# design.net
KiCad netlist of a schematic drawn in Altium Designer
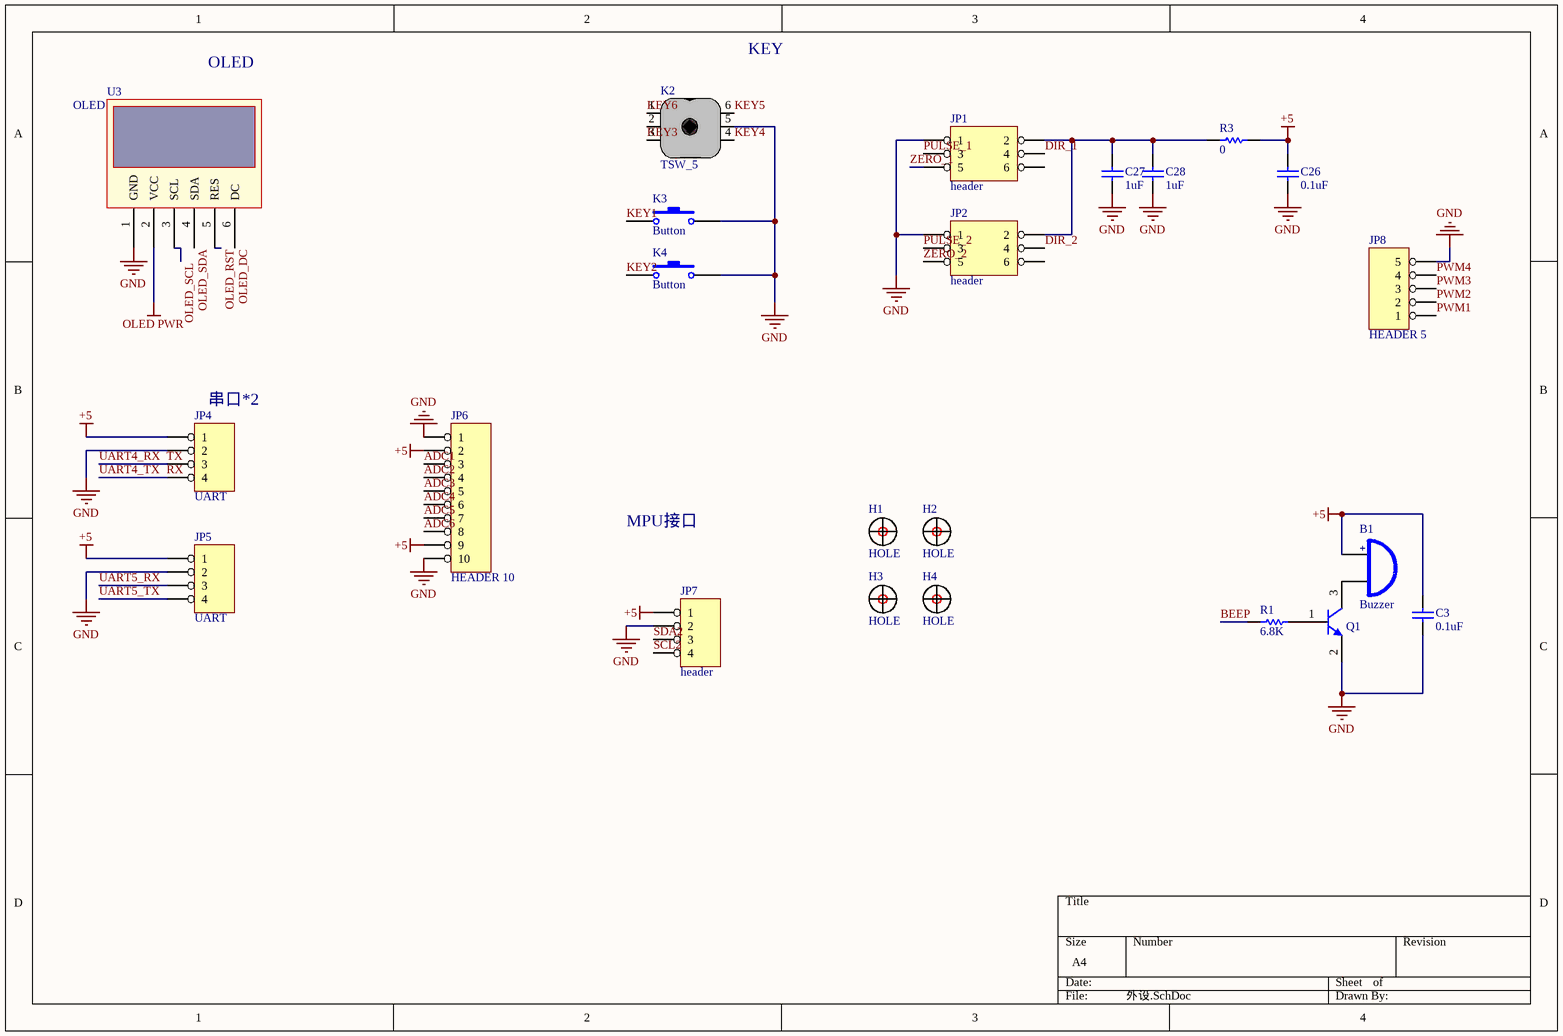
[diagram p0: 外设.SchDoc]

(export (version "E")
  (design (tool "Eeschema 10.0.6"))
  (components
    (comp (ref "B1") (value "Buzzer") (footprint "BUZZ") (libsource (lib "mylib") (part "Buzzer")))
    (comp (ref "C3")
      (value "0.1uF")
      (footprint "0603_C")
      (description "Capacitor")
      (fields (field (name "PUBLISHER") "Altium Limited"))
      (libsource (lib "My Footprint") (part "CAP"))
    )
    (comp (ref "C26")
      (value "0.1uF")
      (footprint "0805_c")
      (description "Capacitor")
      (fields (field (name "PUBLISHER") "Altium Limited"))
      (libsource (lib "LY御用集成库") (part "CAP"))
    )
    (comp (ref "C27")
      (value "1uF")
      (footprint "0805_c")
      (description "Capacitor")
      (fields (field (name "PUBLISHER") "Altium Limited"))
      (libsource (lib "LY御用集成库") (part "CAP"))
    )
    (comp (ref "C28")
      (value "1uF")
      (footprint "0805_c")
      (description "Capacitor")
      (fields (field (name "PUBLISHER") "Altium Limited"))
      (libsource (lib "LY御用集成库") (part "CAP"))
    )
    (comp (ref "H1") (value "HOLE") (footprint "定位孔 Φ3 1") (libsource (lib "LY御用集成库") (part "HOLE")))
    (comp (ref "H2") (value "HOLE") (footprint "定位孔 Φ3 1") (libsource (lib "LY御用集成库") (part "HOLE")))
    (comp (ref "H3") (value "HOLE") (footprint "定位孔 Φ3 1") (libsource (lib "LY御用集成库") (part "HOLE")))
    (comp (ref "H4") (value "HOLE") (footprint "定位孔 Φ3 1") (libsource (lib "LY御用集成库") (part "HOLE")))
    (comp (ref "JP1")
      (value "header")
      (footprint "header2X3")
      (libsource (lib "LY御用集成库") (part "HEADER 3X2"))
    )
    (comp (ref "JP2")
      (value "header")
      (footprint "header2X3")
      (libsource (lib "LY御用集成库") (part "HEADER 3X2"))
    )
    (comp (ref "JP4") (value "UART") (footprint "header4_M") (libsource (lib "LY御用集成库") (part "HEADER 4")))
    (comp (ref "JP5") (value "UART") (footprint "header4") (libsource (lib "LY御用集成库") (part "HEADER 4")))
    (comp (ref "JP6")
      (value "HEADER 10")
      (footprint "HEADER_10P_1.25_UP")
      (libsource (lib "LY御用集成库") (part "HEADER 10"))
    )
    (comp (ref "JP7") (value "header") (footprint "header4") (libsource (lib "LY御用集成库") (part "HEADER 4")))
    (comp (ref "JP8")
      (value "HEADER 5")
      (footprint "HEADER_5P_1.25_RT")
      (libsource (lib "LY御用集成库") (part "HEADER 5"))
    )
    (comp (ref "K2")
      (value "TSW_5")
      (footprint "TSW-10")
      (description "方向开关")
      (libsource (lib "LY御用集成库") (part "TSW_5"))
    )
    (comp (ref "K3")
      (value "Button")
      (footprint "button_2")
      (fields (field (name "PUBLISHER") "Altium Limited"))
      (libsource (lib "LY御用集成库") (part "Button"))
    )
    (comp (ref "K4")
      (value "Button")
      (footprint "button_2")
      (fields (field (name "PUBLISHER") "Altium Limited"))
      (libsource (lib "LY御用集成库") (part "Button"))
    )
    (comp (ref "Q1")
      (value "NPN2")
      (footprint "SOT-23-3")
      (description "贴片")
      (libsource (lib "mylib") (part "NPN2"))
    )
    (comp (ref "R1") (value "6.8K") (footprint "R0603") (libsource (lib "mylib") (part "RES")))
    (comp (ref "R3")
      (value "0")
      (footprint "R0603")
      (description "Resistor")
      (fields (field (name "PUBLISHER") "Altium Limited"))
      (libsource (lib "LY御用集成库") (part "RES"))
    )
    (comp (ref "U3")
      (value "OLED")
      (footprint "0.96寸OLED模块")
      (description "模块")
      (libsource (lib "LY御用集成库") (part "OLED"))
    )
  )
  (nets
    (net (code "1") (name "+5") (class "Default")
      (node (ref "B1") (pin "1") (pinfunction "A_1") (pintype "passive"))
      (node (ref "C26") (pin "2") (pinfunction "2_2") (pintype "passive"))
      (node (ref "C3") (pin "2") (pinfunction "2_2") (pintype "passive"))
      (node (ref "JP4") (pin "1") (pinfunction "1_1") (pintype "passive"))
      (node (ref "JP5") (pin "1") (pinfunction "1_1") (pintype "passive"))
      (node (ref "JP6") (pin "2") (pinfunction "2_2") (pintype "passive"))
      (node (ref "JP6") (pin "9") (pinfunction "9_9") (pintype "passive"))
      (node (ref "JP7") (pin "1") (pinfunction "1_1") (pintype "passive"))
      (node (ref "R3") (pin "1") (pinfunction "1_1") (pintype "passive"))
    )
    (net (code "2") (name "/ADC1") (class "Default")
      (node (ref "JP6") (pin "3") (pinfunction "3_3") (pintype "passive"))
    )
    (net (code "3") (name "/ADC2") (class "Default")
      (node (ref "JP6") (pin "4") (pinfunction "4_4") (pintype "passive"))
    )
    (net (code "4") (name "/ADC3") (class "Default")
      (node (ref "JP6") (pin "5") (pinfunction "5_5") (pintype "passive"))
    )
    (net (code "5") (name "/ADC4") (class "Default")
      (node (ref "JP6") (pin "6") (pinfunction "6_6") (pintype "passive"))
    )
    (net (code "6") (name "/ADC5") (class "Default")
      (node (ref "JP6") (pin "7") (pinfunction "7_7") (pintype "passive"))
    )
    (net (code "7") (name "/ADC6") (class "Default")
      (node (ref "JP6") (pin "8") (pinfunction "8_8") (pintype "passive"))
    )
    (net (code "8") (name "/BEEP") (class "Default")
      (node (ref "R1") (pin "1") (pinfunction "1_1") (pintype "passive"))
    )
    (net (code "9") (name "/DIR_1") (class "Default")
      (node (ref "JP1") (pin "4") (pinfunction "4_4") (pintype "passive"))
    )
    (net (code "10") (name "/DIR_2") (class "Default")
      (node (ref "JP2") (pin "4") (pinfunction "4_4") (pintype "passive"))
    )
    (net (code "11") (name "/KEY1") (class "Default")
      (node (ref "K3") (pin "1") (pinfunction "1_1") (pintype "passive"))
    )
    (net (code "12") (name "/KEY2") (class "Default")
      (node (ref "K4") (pin "1") (pinfunction "1_1") (pintype "passive"))
    )
    (net (code "13") (name "/KEY3") (class "Default") (node (ref "K2") (pin "3") (pintype "passive")))
    (net (code "14") (name "/KEY4") (class "Default") (node (ref "K2") (pin "4") (pintype "passive")))
    (net (code "15") (name "/KEY5") (class "Default") (node (ref "K2") (pin "6") (pintype "passive")))
    (net (code "16") (name "/KEY6") (class "Default") (node (ref "K2") (pin "1") (pintype "passive")))
    (net (code "17") (name "/OLED_DC") (class "Default")
      (node (ref "U3") (pin "6") (pinfunction "DC_6") (pintype "passive"))
    )
    (net (code "18") (name "/OLED_RST") (class "Default")
      (node (ref "U3") (pin "5") (pinfunction "RES_5") (pintype "passive"))
    )
    (net (code "19") (name "/OLED_SCL") (class "Default")
      (node (ref "U3") (pin "3") (pinfunction "SCL_3") (pintype "passive"))
    )
    (net (code "20") (name "/OLED_SDA") (class "Default")
      (node (ref "U3") (pin "4") (pinfunction "SDA_4") (pintype "passive"))
    )
    (net (code "21") (name "/PULSE_1") (class "Default")
      (node (ref "JP1") (pin "3") (pinfunction "3_3") (pintype "passive"))
    )
    (net (code "22") (name "/PULSE_2") (class "Default")
      (node (ref "JP2") (pin "3") (pinfunction "3_3") (pintype "passive"))
    )
    (net (code "23") (name "/PWM1") (class "Default")
      (node (ref "JP8") (pin "1") (pinfunction "1_1") (pintype "passive"))
    )
    (net (code "24") (name "/PWM2") (class "Default")
      (node (ref "JP8") (pin "2") (pinfunction "2_2") (pintype "passive"))
    )
    (net (code "25") (name "/PWM3") (class "Default")
      (node (ref "JP8") (pin "3") (pinfunction "3_3") (pintype "passive"))
    )
    (net (code "26") (name "/PWM4") (class "Default")
      (node (ref "JP8") (pin "4") (pinfunction "4_4") (pintype "passive"))
    )
    (net (code "27") (name "/RX") (class "Default")
      (node (ref "JP4") (pin "4") (pinfunction "4_4") (pintype "passive"))
    )
    (net (code "28") (name "/SCL2") (class "Default")
      (node (ref "JP7") (pin "4") (pinfunction "4_4") (pintype "passive"))
    )
    (net (code "29") (name "/SDA2") (class "Default")
      (node (ref "JP7") (pin "3") (pinfunction "3_3") (pintype "passive"))
    )
    (net (code "30") (name "/TX") (class "Default")
      (node (ref "JP4") (pin "3") (pinfunction "3_3") (pintype "passive"))
    )
    (net (code "31") (name "/UART5_RX") (class "Default")
      (node (ref "JP5") (pin "3") (pinfunction "3_3") (pintype "passive"))
    )
    (net (code "32") (name "/UART5_TX") (class "Default")
      (node (ref "JP5") (pin "4") (pinfunction "4_4") (pintype "passive"))
    )
    (net (code "33") (name "/ZERO_1") (class "Default")
      (node (ref "JP1") (pin "5") (pinfunction "5_5") (pintype "passive"))
    )
    (net (code "34") (name "/ZERO_2") (class "Default")
      (node (ref "JP2") (pin "5") (pinfunction "5_5") (pintype "passive"))
    )
    (net (code "35") (name "GND") (class "Default")
      (node (ref "C26") (pin "1") (pinfunction "1_1") (pintype "passive"))
      (node (ref "C27") (pin "1") (pinfunction "1_1") (pintype "passive"))
      (node (ref "C28") (pin "1") (pinfunction "1_1") (pintype "passive"))
      (node (ref "C3") (pin "1") (pinfunction "1_1") (pintype "passive"))
      (node (ref "JP1") (pin "1") (pinfunction "1_1") (pintype "passive"))
      (node (ref "JP2") (pin "1") (pinfunction "1_1") (pintype "passive"))
      (node (ref "JP4") (pin "2") (pinfunction "2_2") (pintype "passive"))
      (node (ref "JP5") (pin "2") (pinfunction "2_2") (pintype "passive"))
      (node (ref "JP6") (pin "1") (pinfunction "1_1") (pintype "passive"))
      (node (ref "JP6") (pin "10") (pinfunction "10_10") (pintype "passive"))
      (node (ref "JP7") (pin "2") (pinfunction "2_2") (pintype "passive"))
      (node (ref "JP8") (pin "5") (pinfunction "5_5") (pintype "passive"))
      (node (ref "K2") (pin "5") (pintype "passive"))
      (node (ref "K3") (pin "2") (pinfunction "2_2") (pintype "passive"))
      (node (ref "K4") (pin "2") (pinfunction "2_2") (pintype "passive"))
      (node (ref "Q1") (pin "2") (pinfunction "E_2") (pintype "passive"))
      (node (ref "U3") (pin "1") (pinfunction "GND_1") (pintype "passive"))
    )
    (net (code "36") (name "Net-(B1-B)") (class "Default")
      (node (ref "B1") (pin "2") (pinfunction "B_2") (pintype "passive"))
      (node (ref "Q1") (pin "3") (pinfunction "C_3") (pintype "passive"))
    )
    (net (code "37") (name "Net-(C27-Pad2)") (class "Default")
      (node (ref "C27") (pin "2") (pinfunction "2_2") (pintype "passive"))
      (node (ref "C28") (pin "2") (pinfunction "2_2") (pintype "passive"))
      (node (ref "JP1") (pin "2") (pinfunction "2_2") (pintype "passive"))
      (node (ref "JP2") (pin "2") (pinfunction "2_2") (pintype "passive"))
      (node (ref "R3") (pin "2") (pinfunction "2_2") (pintype "passive"))
    )
    (net (code "38") (name "Net-(Q1-B)") (class "Default")
      (node (ref "Q1") (pin "1") (pinfunction "B_1") (pintype "passive"))
      (node (ref "R1") (pin "2") (pinfunction "2_2") (pintype "passive"))
    )
    (net (code "39") (name "OLED PWR") (class "Default")
      (node (ref "U3") (pin "2") (pinfunction "VCC_2") (pintype "passive"))
    )
    (net (code "40") (name "unconnected-(H1-Pad1)") (class "Default")
      (node (ref "H1") (pin "1") (pintype "passive"))
    )
    (net (code "41") (name "unconnected-(H2-Pad1)") (class "Default")
      (node (ref "H2") (pin "1") (pintype "passive"))
    )
    (net (code "42") (name "unconnected-(H3-Pad1)") (class "Default")
      (node (ref "H3") (pin "1") (pintype "passive"))
    )
    (net (code "43") (name "unconnected-(H4-Pad1)") (class "Default")
      (node (ref "H4") (pin "1") (pintype "passive"))
    )
    (net (code "44") (name "unconnected-(JP1-Pad6)") (class "Default")
      (node (ref "JP1") (pin "6") (pinfunction "6_6") (pintype "passive"))
    )
    (net (code "45") (name "unconnected-(JP2-Pad6)") (class "Default")
      (node (ref "JP2") (pin "6") (pinfunction "6_6") (pintype "passive"))
    )
    (net (code "46") (name "unconnected-(K2-Pad2)") (class "Default")
      (node (ref "K2") (pin "2") (pintype "passive"))
    )
  )
)
